# AST1003.net
KiCad netlist of a schematic drawn in EAGLE
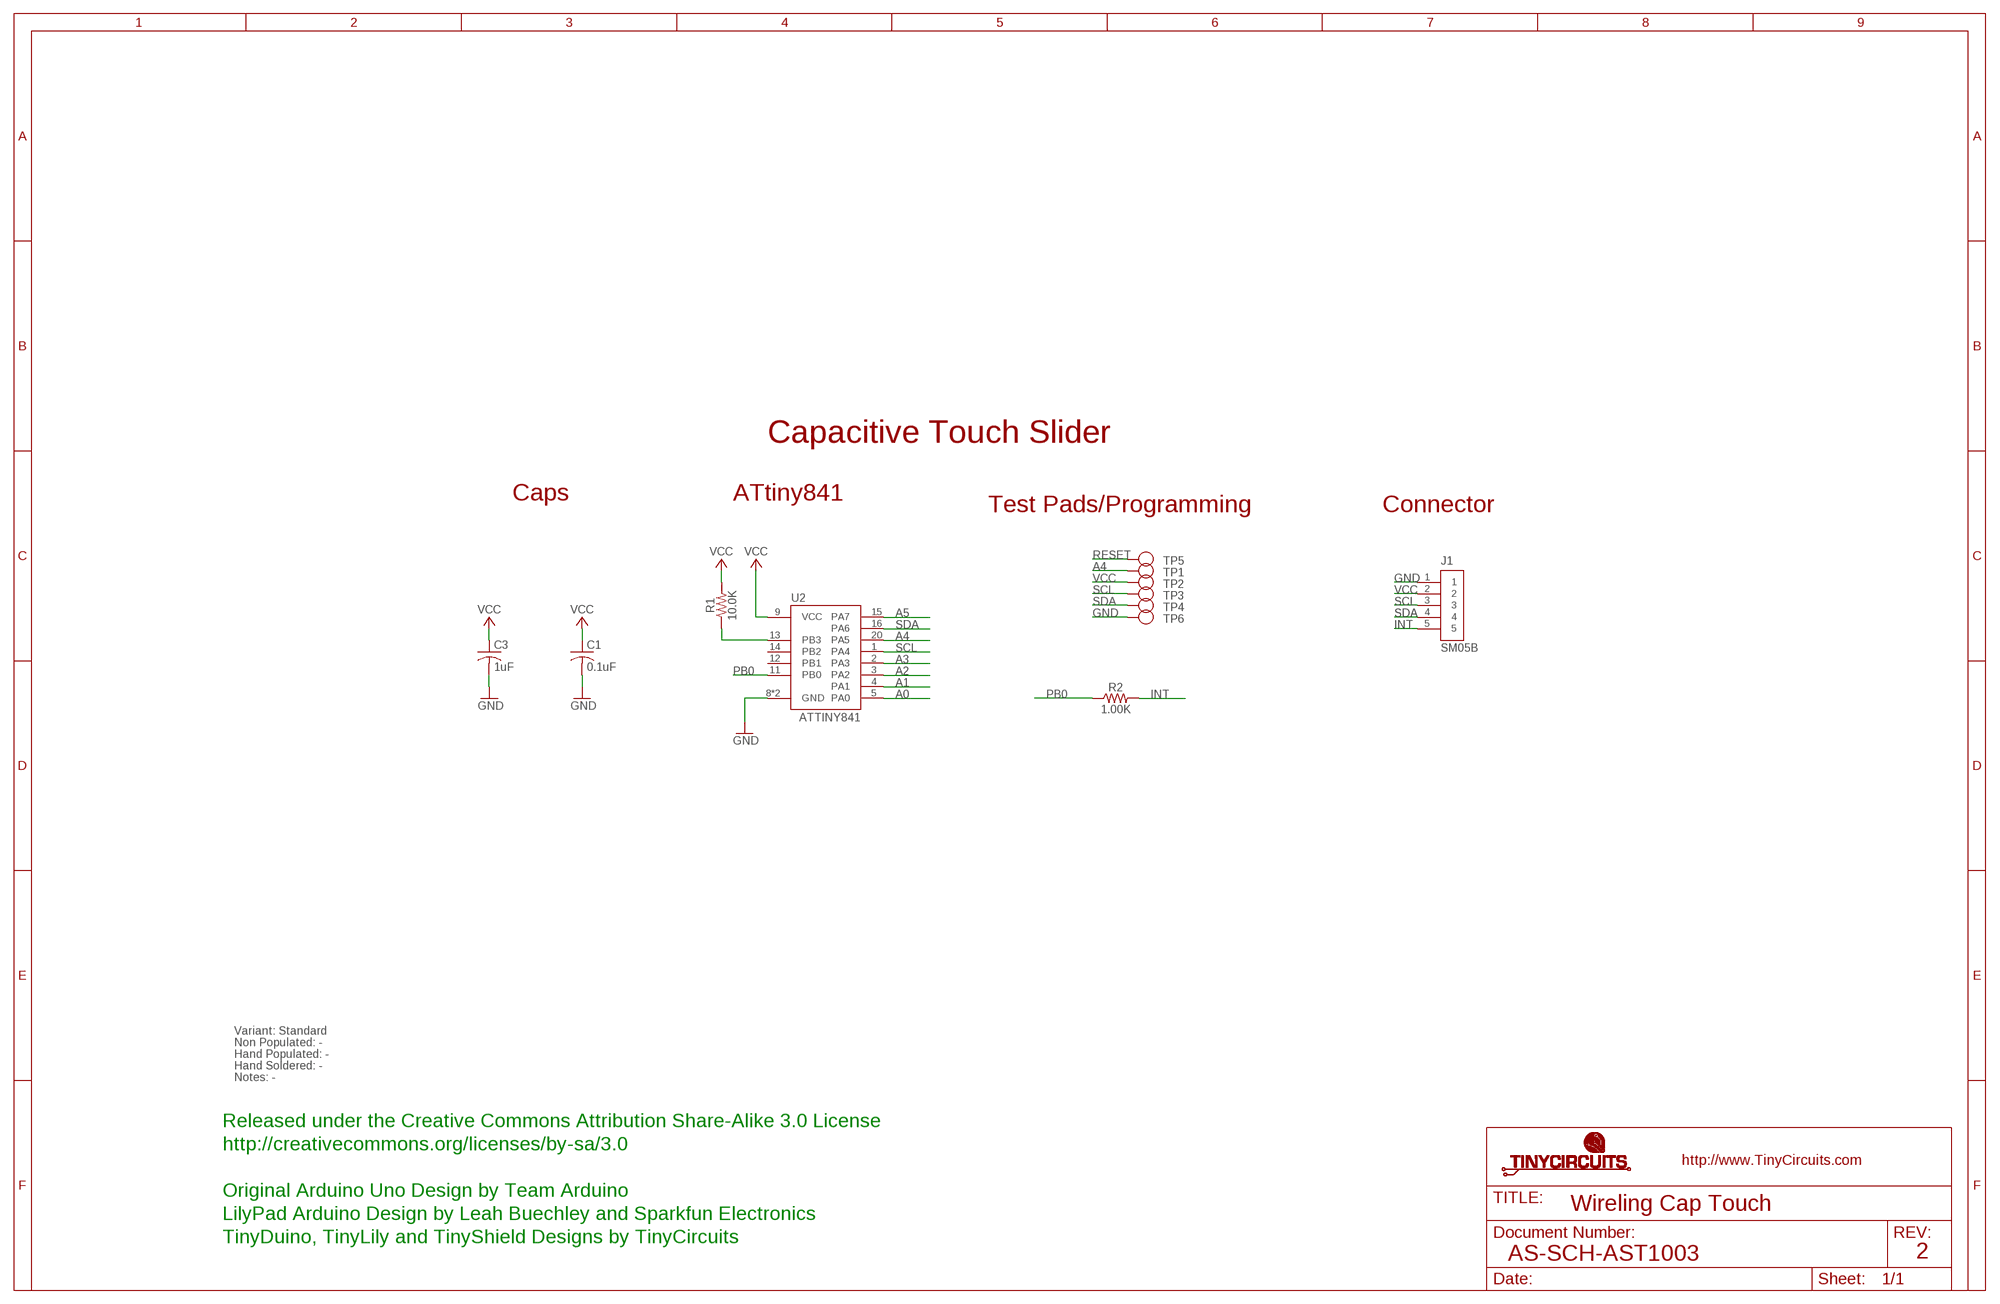
[diagram p0: schematic, sheet 1]

(export (version "E")
  (design (tool "Eeschema 10.0.6"))
  (components
    (comp (ref "C1")
      (value "0.1uF")
      (footprint "eagle-import:C0402")
      (fields (field (name "PARTNO") "AS-ITM-00008"))
      (libsource (lib "eagle-import") (part "AS-ITM-00008"))
    )
    (comp (ref "C3")
      (value "1uF")
      (footprint "eagle-import:C0603")
      (fields (field (name "PARTNO") "AS-ITM-00410") (field (name "PARTNO_1") "AS-ITM-00410"))
      (libsource (lib "eagle-import") (part "AS-ITM-00410"))
    )
    (comp (ref "J1")
      (value "SM05B")
      (footprint "eagle-import:JST_SH_5X1")
      (fields (field (name "PARTNO") "AS-ITM-00340"))
      (libsource (lib "eagle-import") (part "AS-ITM-00340"))
    )
    (comp (ref "R1")
      (value "10.0K")
      (footprint "eagle-import:0402")
      (fields (field (name "PARTNO") "AS-ITM-00032"))
      (libsource (lib "eagle-import") (part "AS-ITM-00032"))
    )
    (comp (ref "R2")
      (value "1.00K")
      (footprint "eagle-import:0402")
      (fields (field (name "PARTNO") "AS-ITM-00003") (field (name "PARTNO_1") "AS-ITM-00003"))
      (libsource (lib "eagle-import") (part "AS-ITM-00003"))
    )
    (comp (ref "TP1")
      (value "TEST_POINT")
      (footprint "eagle-import:TEST_POINT_1MM")
      (libsource (lib "eagle-import") (part "TEST_POINT"))
    )
    (comp (ref "TP2")
      (value "TEST_POINT")
      (footprint "eagle-import:TEST_POINT_1MM")
      (libsource (lib "eagle-import") (part "TEST_POINT"))
    )
    (comp (ref "TP3")
      (value "TEST_POINT")
      (footprint "eagle-import:TEST_POINT_1MM")
      (libsource (lib "eagle-import") (part "TEST_POINT"))
    )
    (comp (ref "TP4")
      (value "TEST_POINT")
      (footprint "eagle-import:TEST_POINT_1MM")
      (libsource (lib "eagle-import") (part "TEST_POINT"))
    )
    (comp (ref "TP5")
      (value "TEST_POINT")
      (footprint "eagle-import:TEST_POINT_1MM")
      (libsource (lib "eagle-import") (part "TEST_POINT"))
    )
    (comp (ref "TP6")
      (value "TEST_POINT")
      (footprint "eagle-import:TEST_POINT_1MM")
      (libsource (lib "eagle-import") (part "TEST_POINT"))
    )
    (comp (ref "U2")
      (value "ATTINY841")
      (footprint "eagle-import:VQFN-20")
      (fields (field (name "PARTNO") "AS-ITM-00255"))
      (libsource (lib "eagle-import") (part "AS-ITM-00255"))
    )
  )
  (nets
    (net (code "1") (name "/A0") (class "Default")
      (node (ref "U2") (pin "5") (pinfunction "PA0_5") (pintype "bidirectional"))
    )
    (net (code "2") (name "/A1") (class "Default")
      (node (ref "U2") (pin "4") (pinfunction "PA1_4") (pintype "bidirectional"))
    )
    (net (code "3") (name "/A2") (class "Default")
      (node (ref "U2") (pin "3") (pinfunction "PA2_3") (pintype "bidirectional"))
    )
    (net (code "4") (name "/A3") (class "Default")
      (node (ref "U2") (pin "2") (pinfunction "PA3_2") (pintype "bidirectional"))
    )
    (net (code "5") (name "/A4") (class "Default")
      (node (ref "TP1") (pin "P$1") (pinfunction "1_P$1") (pintype "bidirectional"))
      (node (ref "U2") (pin "20") (pinfunction "PA5_20") (pintype "bidirectional"))
    )
    (net (code "6") (name "/A5") (class "Default")
      (node (ref "U2") (pin "15") (pinfunction "PA7_15") (pintype "bidirectional"))
    )
    (net (code "7") (name "/INT") (class "Default")
      (node (ref "J1") (pin "5") (pinfunction "5_5") (pintype "bidirectional"))
      (node (ref "R2") (pin "2") (pinfunction "2_2") (pintype "passive"))
    )
    (net (code "8") (name "/PB0") (class "Default")
      (node (ref "R2") (pin "1") (pinfunction "1_1") (pintype "passive"))
      (node (ref "U2") (pin "11") (pinfunction "PB0_11") (pintype "bidirectional"))
    )
    (net (code "9") (name "/RESET") (class "Default")
      (node (ref "R1") (pin "1") (pinfunction "1_1") (pintype "passive"))
      (node (ref "TP5") (pin "P$1") (pinfunction "1_P$1") (pintype "bidirectional"))
      (node (ref "U2") (pin "13") (pinfunction "PB3_13") (pintype "bidirectional"))
    )
    (net (code "10") (name "/SCL") (class "Default")
      (node (ref "J1") (pin "3") (pinfunction "3_3") (pintype "bidirectional"))
      (node (ref "TP3") (pin "P$1") (pinfunction "1_P$1") (pintype "bidirectional"))
      (node (ref "U2") (pin "1") (pinfunction "PA4_1") (pintype "bidirectional"))
    )
    (net (code "11") (name "/SDA") (class "Default")
      (node (ref "J1") (pin "4") (pinfunction "4_4") (pintype "bidirectional"))
      (node (ref "TP4") (pin "P$1") (pinfunction "1_P$1") (pintype "bidirectional"))
      (node (ref "U2") (pin "16") (pinfunction "PA6_16") (pintype "bidirectional"))
    )
    (net (code "12") (name "GND") (class "Default")
      (node (ref "C1") (pin "2") (pinfunction "2_2") (pintype "passive"))
      (node (ref "C3") (pin "2") (pinfunction "2_2") (pintype "passive"))
      (node (ref "J1") (pin "1") (pinfunction "1_1") (pintype "bidirectional"))
      (node (ref "TP6") (pin "P$1") (pinfunction "1_P$1") (pintype "bidirectional"))
      (node (ref "U2") (pin "8") (pinfunction "GND_8") (pintype "bidirectional"))
      (node (ref "U2") (pin "PAD") (pinfunction "GND_PAD") (pintype "bidirectional"))
    )
    (net (code "13") (name "VCC") (class "Default")
      (node (ref "C1") (pin "1") (pinfunction "1_1") (pintype "passive"))
      (node (ref "C3") (pin "1") (pinfunction "1_1") (pintype "passive"))
      (node (ref "J1") (pin "2") (pinfunction "2_2") (pintype "bidirectional"))
      (node (ref "R1") (pin "2") (pinfunction "2_2") (pintype "passive"))
      (node (ref "TP2") (pin "P$1") (pinfunction "1_P$1") (pintype "bidirectional"))
      (node (ref "U2") (pin "9") (pinfunction "VCC_9") (pintype "bidirectional"))
    )
    (net (code "14") (name "unconnected-(U2-PB1-Pad12)") (class "Default")
      (node (ref "U2") (pin "12") (pinfunction "PB1_12") (pintype "bidirectional"))
    )
    (net (code "15") (name "unconnected-(U2-PB2-Pad14)") (class "Default")
      (node (ref "U2") (pin "14") (pinfunction "PB2_14") (pintype "bidirectional"))
    )
  )
)
